# BTX.net
KiCad netlist of a schematic drawn in EAGLE
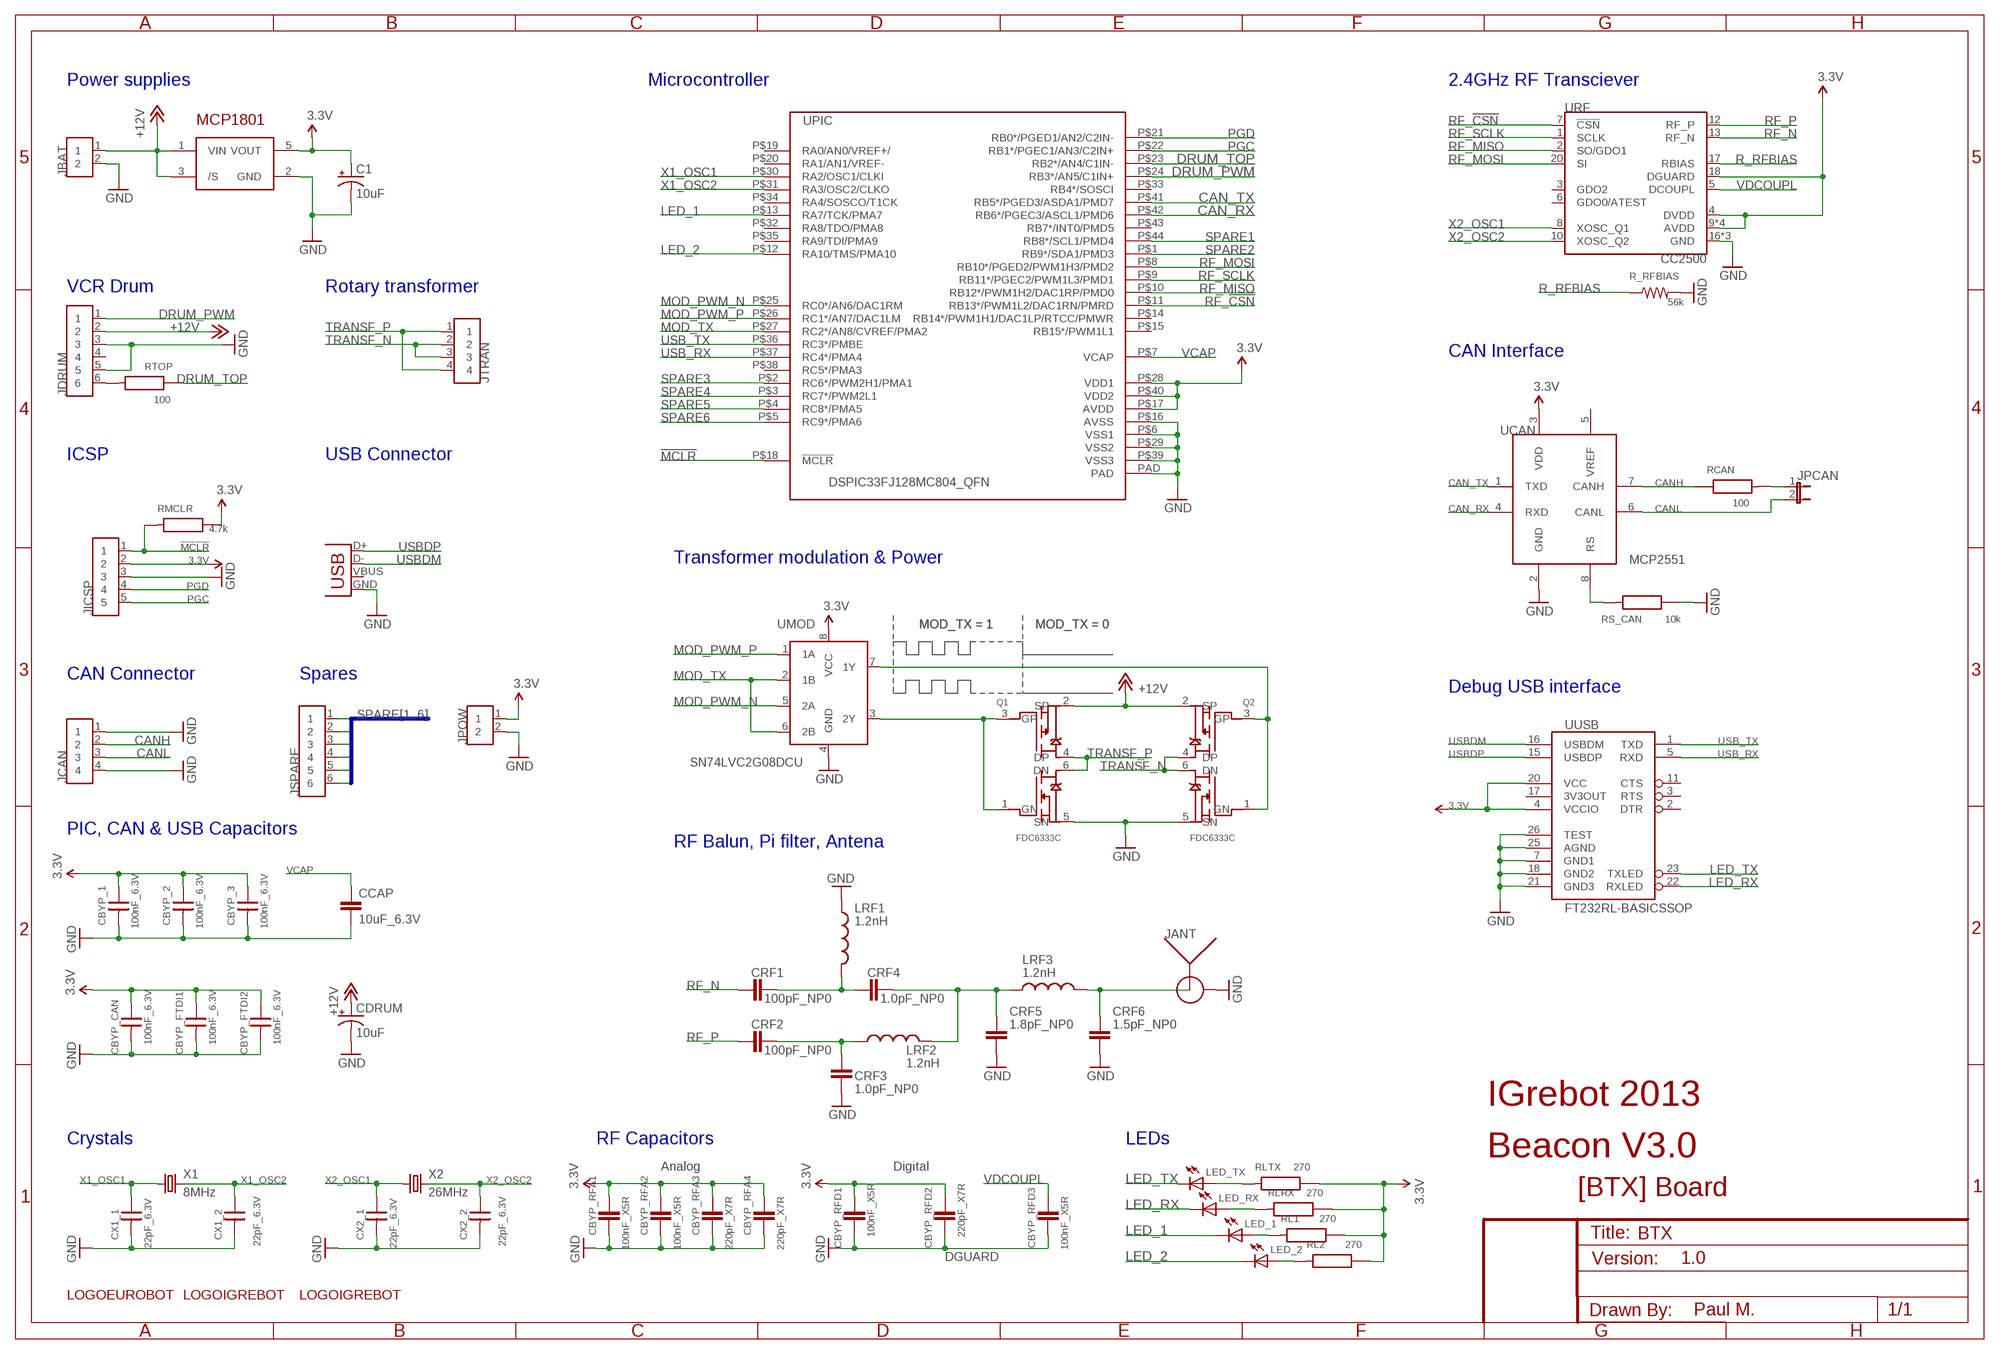
[diagram p0: schematic, sheet 1]

(export (version "E")
  (design (tool "Eeschema 10.0.6"))
  (components
    (comp (ref "C1")
      (value "10uF")
      (footprint "eagle-import:PANASONIC_C")
      (libsource (lib "eagle-import") (part "CAP_POLC"))
    )
    (comp (ref "CBYP_1")
      (value "100nF_6.3V")
      (footprint "eagle-import:R0603")
      (libsource (lib "eagle-import") (part "C0603"))
    )
    (comp (ref "CBYP_2")
      (value "100nF_6.3V")
      (footprint "eagle-import:R0603")
      (libsource (lib "eagle-import") (part "C0603"))
    )
    (comp (ref "CBYP_3")
      (value "100nF_6.3V")
      (footprint "eagle-import:R0603")
      (libsource (lib "eagle-import") (part "C0603"))
    )
    (comp (ref "CBYP_CAN")
      (value "100nF_6.3V")
      (footprint "eagle-import:R0603")
      (libsource (lib "eagle-import") (part "C0603"))
    )
    (comp (ref "CBYP_FTDI1")
      (value "100nF_6.3V")
      (footprint "eagle-import:R0603")
      (libsource (lib "eagle-import") (part "C0603"))
    )
    (comp (ref "CBYP_FTDI2")
      (value "100nF_6.3V")
      (footprint "eagle-import:R0603")
      (libsource (lib "eagle-import") (part "C0603"))
    )
    (comp (ref "CBYP_RFA1")
      (value "100nF_X5R")
      (footprint "eagle-import:0402-CAP")
      (libsource (lib "eagle-import") (part "SparkFun-Passives_CAP0402-CAP"))
    )
    (comp (ref "CBYP_RFA2")
      (value "100nF_X5R")
      (footprint "eagle-import:0402-CAP")
      (libsource (lib "eagle-import") (part "SparkFun-Passives_CAP0402-CAP"))
    )
    (comp (ref "CBYP_RFA3")
      (value "220pF_X7R")
      (footprint "eagle-import:0402-CAP")
      (libsource (lib "eagle-import") (part "SparkFun-Passives_CAP0402-CAP"))
    )
    (comp (ref "CBYP_RFA4")
      (value "220pF_X7R")
      (footprint "eagle-import:0402-CAP")
      (libsource (lib "eagle-import") (part "SparkFun-Passives_CAP0402-CAP"))
    )
    (comp (ref "CBYP_RFD1")
      (value "100nF_X5R")
      (footprint "eagle-import:0402-CAP")
      (libsource (lib "eagle-import") (part "SparkFun-Passives_CAP0402-CAP"))
    )
    (comp (ref "CBYP_RFD2")
      (value "220pF_X7R")
      (footprint "eagle-import:0402-CAP")
      (libsource (lib "eagle-import") (part "SparkFun-Passives_CAP0402-CAP"))
    )
    (comp (ref "CBYP_RFD3")
      (value "100nF_X5R")
      (footprint "eagle-import:0402-CAP")
      (libsource (lib "eagle-import") (part "SparkFun-Passives_CAP0402-CAP"))
    )
    (comp (ref "CCAP")
      (value "10uF_6.3V")
      (footprint "eagle-import:1206")
      (libsource (lib "eagle-import") (part "CAP1206"))
    )
    (comp (ref "CDRUM")
      (value "10uF")
      (footprint "eagle-import:PANASONIC_C")
      (libsource (lib "eagle-import") (part "CAP_POLC"))
    )
    (comp (ref "CRF1")
      (value "100pF_NP0")
      (footprint "eagle-import:0402-CAP")
      (libsource (lib "eagle-import") (part "SparkFun-Passives_CAP0402-CAP"))
    )
    (comp (ref "CRF2")
      (value "100pF_NP0")
      (footprint "eagle-import:0402-CAP")
      (libsource (lib "eagle-import") (part "SparkFun-Passives_CAP0402-CAP"))
    )
    (comp (ref "CRF3")
      (value "1.0pF_NP0")
      (footprint "eagle-import:0402-CAP")
      (libsource (lib "eagle-import") (part "SparkFun-Passives_CAP0402-CAP"))
    )
    (comp (ref "CRF4")
      (value "1.0pF_NP0")
      (footprint "eagle-import:0402-CAP")
      (libsource (lib "eagle-import") (part "SparkFun-Passives_CAP0402-CAP"))
    )
    (comp (ref "CRF5")
      (value "1.8pF_NP0")
      (footprint "eagle-import:0402-CAP")
      (libsource (lib "eagle-import") (part "SparkFun-Passives_CAP0402-CAP"))
    )
    (comp (ref "CRF6")
      (value "1.5pF_NP0")
      (footprint "eagle-import:0402-CAP")
      (libsource (lib "eagle-import") (part "SparkFun-Passives_CAP0402-CAP"))
    )
    (comp (ref "CX1_1")
      (value "22pF_6.3V")
      (footprint "eagle-import:R0603")
      (libsource (lib "eagle-import") (part "C0603"))
    )
    (comp (ref "CX1_2")
      (value "22pF_6.3V")
      (footprint "eagle-import:R0603")
      (libsource (lib "eagle-import") (part "C0603"))
    )
    (comp (ref "CX2_1")
      (value "22pF_6.3V")
      (footprint "eagle-import:R0603")
      (libsource (lib "eagle-import") (part "C0603"))
    )
    (comp (ref "CX2_2")
      (value "22pF_6.3V")
      (footprint "eagle-import:R0603")
      (libsource (lib "eagle-import") (part "C0603"))
    )
    (comp (ref "JANT")
      (value "ENG_CD_1814400_C1")
      (footprint "eagle-import:SMA-PCB-ANGLE")
      (libsource (lib "eagle-import") (part "ENG_CD_1814400_C1"))
    )
    (comp (ref "JBAT")
      (value "MULTICOMP_PA001-2")
      (footprint "eagle-import:CON2-5.00")
      (libsource (lib "eagle-import") (part "MULTICOMP_PA001-2"))
    )
    (comp (ref "JCAN")
      (value "SIL4")
      (footprint "eagle-import:CON4-2.54")
      (libsource (lib "eagle-import") (part "SIL4"))
    )
    (comp (ref "JDRUM")
      (value "SIL6")
      (footprint "eagle-import:CON6-2.54")
      (libsource (lib "eagle-import") (part "SIL6"))
    )
    (comp (ref "JICSP")
      (value "SIL5")
      (footprint "eagle-import:CON5-2.54")
      (libsource (lib "eagle-import") (part "SIL5"))
    )
    (comp (ref "JPCAN")
      (value "JUMPER-2PTH_LOCK")
      (footprint "eagle-import:1X02_LOCK")
      (libsource (lib "eagle-import") (part "JUMPER-2PTH_LOCK"))
    )
    (comp (ref "JPOW")
      (value "SIL2")
      (footprint "eagle-import:CON2-2.54")
      (libsource (lib "eagle-import") (part "SIL2"))
    )
    (comp (ref "JSPARE")
      (value "SIL6")
      (footprint "eagle-import:CON6-2.54")
      (libsource (lib "eagle-import") (part "SIL6"))
    )
    (comp (ref "JTRAN")
      (value "SIL4")
      (footprint "eagle-import:CON4-2.54")
      (libsource (lib "eagle-import") (part "SIL4"))
    )
    (comp (ref "JUSB")
      (value "USBSMD")
      (footprint "eagle-import:USB-MINIB")
      (libsource (lib "eagle-import") (part "USBSMD"))
    )
    (comp (ref "LED_1")
      (value "LED0603")
      (footprint "eagle-import:LED-0603")
      (libsource (lib "eagle-import") (part "LED0603"))
    )
    (comp (ref "LED_2")
      (value "LED0603")
      (footprint "eagle-import:LED-0603")
      (libsource (lib "eagle-import") (part "LED0603"))
    )
    (comp (ref "LED_RX")
      (value "LED0603")
      (footprint "eagle-import:LED-0603")
      (libsource (lib "eagle-import") (part "LED0603"))
    )
    (comp (ref "LED_TX")
      (value "LED0603")
      (footprint "eagle-import:LED-0603")
      (libsource (lib "eagle-import") (part "LED0603"))
    )
    (comp (ref "LRF1")
      (value "1.2nH")
      (footprint "eagle-import:C0402")
      (libsource (lib "eagle-import") (part "INDUCTOR0402"))
    )
    (comp (ref "LRF2")
      (value "1.2nH")
      (footprint "eagle-import:C0402")
      (libsource (lib "eagle-import") (part "INDUCTOR0402"))
    )
    (comp (ref "LRF3")
      (value "1.2nH")
      (footprint "eagle-import:C0402")
      (libsource (lib "eagle-import") (part "INDUCTOR0402"))
    )
    (comp (ref "Q1")
      (value "FDC6333C")
      (footprint "eagle-import:SSOT6")
      (libsource (lib "eagle-import") (part "FDC6333C"))
    )
    (comp (ref "Q2")
      (value "FDC6333C")
      (footprint "eagle-import:SSOT6")
      (libsource (lib "eagle-import") (part "FDC6333C"))
    )
    (comp (ref "RCAN")
      (value "100")
      (footprint "eagle-import:R0603")
      (libsource (lib "eagle-import") (part "R0603"))
    )
    (comp (ref "RL1")
      (value "270")
      (footprint "eagle-import:R0603")
      (libsource (lib "eagle-import") (part "R0603"))
    )
    (comp (ref "RL2")
      (value "270")
      (footprint "eagle-import:R0603")
      (libsource (lib "eagle-import") (part "R0603"))
    )
    (comp (ref "RLRX")
      (value "270")
      (footprint "eagle-import:R0603")
      (libsource (lib "eagle-import") (part "R0603"))
    )
    (comp (ref "RLTX")
      (value "270")
      (footprint "eagle-import:R0603")
      (libsource (lib "eagle-import") (part "R0603"))
    )
    (comp (ref "RMCLR")
      (value "4.7k")
      (footprint "eagle-import:R0603")
      (libsource (lib "eagle-import") (part "R0603"))
    )
    (comp (ref "RS_CAN")
      (value "10k")
      (footprint "eagle-import:R0603")
      (libsource (lib "eagle-import") (part "R0603"))
    )
    (comp (ref "RTOP")
      (value "100")
      (footprint "eagle-import:R0603")
      (libsource (lib "eagle-import") (part "R0603"))
    )
    (comp (ref "R_RFBIAS")
      (value "56k")
      (footprint "eagle-import:0402-RES")
      (libsource (lib "eagle-import") (part "RESISTOR0402-RES"))
    )
    (comp (ref "U$3")
      (value "LOGOEUROBOT")
      (footprint "eagle-import:LOGO_EUROBOT_1")
      (libsource (lib "eagle-import") (part "LOGOEUROBOT"))
    )
    (comp (ref "U$5")
      (value "LOGOIGREBOT")
      (footprint "eagle-import:LOGO_IGREBOT")
      (libsource (lib "eagle-import") (part "LOGOIGREBOT"))
    )
    (comp (ref "U$9")
      (value "LOGOIGREBOT")
      (footprint "eagle-import:LOGO_IGREBOT")
      (libsource (lib "eagle-import") (part "LOGOIGREBOT"))
    )
    (comp (ref "UCAN")
      (value "MCP2551")
      (footprint "eagle-import:SO-08")
      (libsource (lib "eagle-import") (part "MCP2551"))
    )
    (comp (ref "UMOD")
      (value "SN74LVC2G08DCU")
      (footprint "eagle-import:DCU8")
      (libsource (lib "eagle-import") (part "SN74LVC2G08DCU"))
    )
    (comp (ref "UPIC")
      (value "DSPIC33FJ128MC804_QFN")
      (footprint "eagle-import:QFN44-8X8")
      (libsource (lib "eagle-import") (part "DSPIC33FJ128MC804_QFN"))
    )
    (comp (ref "UREG")
      (value "MCP1801")
      (footprint "eagle-import:SOT23-5L")
      (libsource (lib "eagle-import") (part "MCP1801"))
    )
    (comp (ref "URF")
      (value "CC2500")
      (footprint "eagle-import:QFN20-0.5")
      (libsource (lib "eagle-import") (part "CC2500"))
    )
    (comp (ref "UUSB")
      (value "FT232RL-BASICSSOP")
      (footprint "eagle-import:SSOP28DB")
      (libsource (lib "eagle-import") (part "FT232RL-BASICSSOP"))
    )
    (comp (ref "X1")
      (value "8MHz")
      (footprint "eagle-import:XTAL_4.9-1.8")
      (libsource (lib "eagle-import") (part "XTAL4.8_1.8"))
    )
    (comp (ref "X2")
      (value "26MHz")
      (footprint "eagle-import:XTAL_4.9-1.8")
      (libsource (lib "eagle-import") (part "XTAL4.8_1.8"))
    )
  )
  (nets
    (net (code "1") (name "+12V") (class "Default")
      (node (ref "CDRUM") (pin "+") (pinfunction "+_+") (pintype "passive"))
      (node (ref "JBAT") (pin "1") (pinfunction "1_1") (pintype "bidirectional"))
      (node (ref "JDRUM") (pin "2") (pinfunction "2_2") (pintype "bidirectional"))
      (node (ref "Q1") (pin "2") (pinfunction "SP_2") (pintype "bidirectional"))
      (node (ref "Q2") (pin "2") (pinfunction "SP_2") (pintype "bidirectional"))
      (node (ref "UREG") (pin "1") (pinfunction "VIN_1") (pintype "bidirectional"))
      (node (ref "UREG") (pin "3") (pinfunction "/S_3") (pintype "bidirectional"))
    )
    (net (code "2") (name "/CANH") (class "Default")
      (node (ref "JCAN") (pin "2") (pinfunction "2_2") (pintype "bidirectional"))
      (node (ref "RCAN") (pin "1") (pinfunction "1_1") (pintype "bidirectional"))
      (node (ref "UCAN") (pin "7") (pinfunction "CANH_7") (pintype "bidirectional"))
    )
    (net (code "3") (name "/CANL") (class "Default")
      (node (ref "JCAN") (pin "3") (pinfunction "3_3") (pintype "bidirectional"))
      (node (ref "JPCAN") (pin "2") (pinfunction "2_2") (pintype "passive"))
      (node (ref "UCAN") (pin "6") (pinfunction "CANL_6") (pintype "bidirectional"))
    )
    (net (code "4") (name "/CAN_RX") (class "Default")
      (node (ref "UCAN") (pin "4") (pinfunction "RXD_4") (pintype "bidirectional"))
      (node (ref "UPIC") (pin "P$42") (pinfunction "RB6*/PGEC3/ASCL1/PMD6_P$42") (pintype "bidirectional"))
    )
    (net (code "5") (name "/CAN_TX") (class "Default")
      (node (ref "UCAN") (pin "1") (pinfunction "TXD_1") (pintype "bidirectional"))
      (node (ref "UPIC") (pin "P$41") (pinfunction "RB5*/PGED3/ASDA1/PMD7_P$41") (pintype "bidirectional"))
    )
    (net (code "6") (name "/DRUM_PWM") (class "Default")
      (node (ref "JDRUM") (pin "1") (pinfunction "1_1") (pintype "bidirectional"))
      (node (ref "UPIC") (pin "P$24") (pinfunction "RB3*/AN5/C1IN+_P$24") (pintype "bidirectional"))
    )
    (net (code "7") (name "/DRUM_TOP") (class "Default")
      (node (ref "RTOP") (pin "1") (pinfunction "1_1") (pintype "bidirectional"))
      (node (ref "UPIC") (pin "P$23") (pinfunction "RB2*/AN4/C1IN-_P$23") (pintype "bidirectional"))
    )
    (net (code "8") (name "/LED_1") (class "Default")
      (node (ref "LED_1") (pin "C") (pinfunction "C_C") (pintype "passive"))
      (node (ref "UPIC") (pin "P$13") (pinfunction "RA7/TCK/PMA7_P$13") (pintype "bidirectional"))
    )
    (net (code "9") (name "/LED_2") (class "Default")
      (node (ref "LED_2") (pin "C") (pinfunction "C_C") (pintype "passive"))
      (node (ref "UPIC") (pin "P$12") (pinfunction "RA10/TMS/PMA10_P$12") (pintype "bidirectional"))
    )
    (net (code "10") (name "/LED_RX") (class "Default")
      (node (ref "LED_RX") (pin "C") (pinfunction "C_C") (pintype "passive"))
      (node (ref "UUSB") (pin "22") (pinfunction "RXLED_22") (pintype "bidirectional"))
    )
    (net (code "11") (name "/LED_TX") (class "Default")
      (node (ref "LED_TX") (pin "C") (pinfunction "C_C") (pintype "passive"))
      (node (ref "UUSB") (pin "23") (pinfunction "TXLED_23") (pintype "bidirectional"))
    )
    (net (code "12") (name "/MOD_PWM_N") (class "Default")
      (node (ref "UMOD") (pin "5") (pinfunction "2A_5") (pintype "bidirectional"))
      (node (ref "UPIC") (pin "P$25") (pinfunction "RC0*/AN6/DAC1RM_P$25") (pintype "bidirectional"))
    )
    (net (code "13") (name "/MOD_PWM_P") (class "Default")
      (node (ref "UMOD") (pin "1") (pinfunction "1A_1") (pintype "bidirectional"))
      (node (ref "UPIC") (pin "P$26") (pinfunction "RC1*/AN7/DAC1LM_P$26") (pintype "bidirectional"))
    )
    (net (code "14") (name "/MOD_TX") (class "Default")
      (node (ref "UMOD") (pin "2") (pinfunction "1B_2") (pintype "bidirectional"))
      (node (ref "UMOD") (pin "6") (pinfunction "2B_6") (pintype "bidirectional"))
      (node (ref "UPIC") (pin "P$27") (pinfunction "RC2*/AN8/CVREF/PMA2_P$27") (pintype "bidirectional"))
    )
    (net (code "15") (name "/PGC") (class "Default")
      (node (ref "JICSP") (pin "5") (pinfunction "5_5") (pintype "bidirectional"))
      (node (ref "UPIC") (pin "P$22") (pinfunction "RB1*/PGEC1/AN3/C2IN+_P$22") (pintype "bidirectional"))
    )
    (net (code "16") (name "/PGD") (class "Default")
      (node (ref "JICSP") (pin "4") (pinfunction "4_4") (pintype "bidirectional"))
      (node (ref "UPIC") (pin "P$21") (pinfunction "RB0*/PGED1/AN2/C2IN-_P$21") (pintype "bidirectional"))
    )
    (net (code "17") (name "/RF_MISO") (class "Default")
      (node (ref "UPIC") (pin "P$10") (pinfunction "RB12*/PWM1H2/DAC1RP/PMD0_P$10") (pintype "bidirectional"))
      (node (ref "URF") (pin "2") (pinfunction "SO/GDO1_2") (pintype "bidirectional"))
    )
    (net (code "18") (name "/RF_MOSI") (class "Default")
      (node (ref "UPIC") (pin "P$8") (pinfunction "RB10*/PGED2/PWM1H3/PMD2_P$8") (pintype "bidirectional"))
      (node (ref "URF") (pin "20") (pinfunction "SI_20") (pintype "bidirectional"))
    )
    (net (code "19") (name "/RF_N") (class "Default")
      (node (ref "CRF1") (pin "1") (pinfunction "1_1") (pintype "passive"))
      (node (ref "URF") (pin "13") (pinfunction "RF_N_13") (pintype "bidirectional"))
    )
    (net (code "20") (name "/RF_P") (class "Default")
      (node (ref "CRF2") (pin "1") (pinfunction "1_1") (pintype "passive"))
      (node (ref "URF") (pin "12") (pinfunction "RF_P_12") (pintype "bidirectional"))
    )
    (net (code "21") (name "/RF_SCLK") (class "Default")
      (node (ref "UPIC") (pin "P$9") (pinfunction "RB11*/PGEC2/PWM1L3/PMD1_P$9") (pintype "bidirectional"))
      (node (ref "URF") (pin "1") (pinfunction "SCLK_1") (pintype "bidirectional"))
    )
    (net (code "22") (name "/RF_~{CSN}") (class "Default")
      (node (ref "UPIC") (pin "P$11") (pinfunction "RB13*/PWM1L2/DAC1RN/PMRD_P$11") (pintype "bidirectional"))
      (node (ref "URF") (pin "7") (pinfunction "~{CSN}_7") (pintype "bidirectional"))
    )
    (net (code "23") (name "/R_RFBIAS") (class "Default")
      (node (ref "R_RFBIAS") (pin "1") (pinfunction "1_1") (pintype "passive"))
      (node (ref "URF") (pin "17") (pinfunction "RBIAS_17") (pintype "bidirectional"))
    )
    (net (code "24") (name "/SPARE1") (class "Default")
      (node (ref "JSPARE") (pin "1") (pinfunction "1_1") (pintype "bidirectional"))
      (node (ref "UPIC") (pin "P$44") (pinfunction "RB8*/SCL1/PMD4_P$44") (pintype "bidirectional"))
    )
    (net (code "25") (name "/SPARE2") (class "Default")
      (node (ref "JSPARE") (pin "2") (pinfunction "2_2") (pintype "bidirectional"))
      (node (ref "UPIC") (pin "P$1") (pinfunction "RB9*/SDA1/PMD3_P$1") (pintype "bidirectional"))
    )
    (net (code "26") (name "/SPARE3") (class "Default")
      (node (ref "JSPARE") (pin "3") (pinfunction "3_3") (pintype "bidirectional"))
      (node (ref "UPIC") (pin "P$2") (pinfunction "RC6*/PWM2H1/PMA1_P$2") (pintype "bidirectional"))
    )
    (net (code "27") (name "/SPARE4") (class "Default")
      (node (ref "JSPARE") (pin "4") (pinfunction "4_4") (pintype "bidirectional"))
      (node (ref "UPIC") (pin "P$3") (pinfunction "RC7*/PWM2L1_P$3") (pintype "bidirectional"))
    )
    (net (code "28") (name "/SPARE5") (class "Default")
      (node (ref "JSPARE") (pin "5") (pinfunction "5_5") (pintype "bidirectional"))
      (node (ref "UPIC") (pin "P$4") (pinfunction "RC8*/PMA5_P$4") (pintype "bidirectional"))
    )
    (net (code "29") (name "/SPARE6") (class "Default")
      (node (ref "JSPARE") (pin "6") (pinfunction "6_6") (pintype "bidirectional"))
      (node (ref "UPIC") (pin "P$5") (pinfunction "RC9*/PMA6_P$5") (pintype "bidirectional"))
    )
    (net (code "31") (name "/TRANSF_N") (class "Default")
      (node (ref "JTRAN") (pin "2") (pinfunction "2_2") (pintype "bidirectional"))
      (node (ref "JTRAN") (pin "3") (pinfunction "3_3") (pintype "bidirectional"))
      (node (ref "Q2") (pin "4") (pinfunction "DP_4") (pintype "bidirectional"))
      (node (ref "Q2") (pin "6") (pinfunction "DN_6") (pintype "bidirectional"))
    )
    (net (code "32") (name "/TRANSF_P") (class "Default")
      (node (ref "JTRAN") (pin "1") (pinfunction "1_1") (pintype "bidirectional"))
      (node (ref "JTRAN") (pin "4") (pinfunction "4_4") (pintype "bidirectional"))
      (node (ref "Q1") (pin "4") (pinfunction "DP_4") (pintype "bidirectional"))
      (node (ref "Q1") (pin "6") (pinfunction "DN_6") (pintype "bidirectional"))
    )
    (net (code "33") (name "/USBDM") (class "Default")
      (node (ref "JUSB") (pin "D-") (pinfunction "D-_D-") (pintype "bidirectional"))
      (node (ref "UUSB") (pin "16") (pinfunction "USBDM_16") (pintype "bidirectional"))
    )
    (net (code "34") (name "/USBDP") (class "Default")
      (node (ref "JUSB") (pin "D+") (pinfunction "D+_D+") (pintype "bidirectional"))
      (node (ref "UUSB") (pin "15") (pinfunction "USBDP_15") (pintype "bidirectional"))
    )
    (net (code "35") (name "/USB_RX") (class "Default")
      (node (ref "UPIC") (pin "P$37") (pinfunction "RC4*/PMA4_P$37") (pintype "bidirectional"))
      (node (ref "UUSB") (pin "5") (pinfunction "RXD_5") (pintype "input"))
    )
    (net (code "36") (name "/USB_TX") (class "Default")
      (node (ref "UPIC") (pin "P$36") (pinfunction "RC3*/PMBE_P$36") (pintype "bidirectional"))
      (node (ref "UUSB") (pin "1") (pinfunction "TXD_1") (pintype "output"))
    )
    (net (code "37") (name "/VCAP") (class "Default")
      (node (ref "CCAP") (pin "1") (pinfunction "1_1") (pintype "passive"))
      (node (ref "UPIC") (pin "P$7") (pinfunction "VCAP_P$7") (pintype "bidirectional"))
    )
    (net (code "38") (name "/VDCOUPL") (class "Default")
      (node (ref "CBYP_RFD3") (pin "2") (pinfunction "2_2") (pintype "passive"))
      (node (ref "URF") (pin "5") (pinfunction "DCOUPL_5") (pintype "bidirectional"))
    )
    (net (code "39") (name "/X1_OSC1") (class "Default")
      (node (ref "CX1_1") (pin "1") (pinfunction "1_1") (pintype "bidirectional"))
      (node (ref "UPIC") (pin "P$30") (pinfunction "RA2/OSC1/CLKI_P$30") (pintype "bidirectional"))
      (node (ref "X1") (pin "P$1") (pinfunction "1_P$1") (pintype "passive"))
    )
    (net (code "40") (name "/X1_OSC2") (class "Default")
      (node (ref "CX1_2") (pin "1") (pinfunction "1_1") (pintype "bidirectional"))
      (node (ref "UPIC") (pin "P$31") (pinfunction "RA3/OSC2/CLKO_P$31") (pintype "bidirectional"))
      (node (ref "X1") (pin "P$2") (pinfunction "2_P$2") (pintype "passive"))
    )
    (net (code "41") (name "/X2_OSC1") (class "Default")
      (node (ref "CX2_1") (pin "1") (pinfunction "1_1") (pintype "bidirectional"))
      (node (ref "URF") (pin "8") (pinfunction "XOSC_Q1_8") (pintype "bidirectional"))
      (node (ref "X2") (pin "P$1") (pinfunction "1_P$1") (pintype "passive"))
    )
    (net (code "42") (name "/X2_OSC2") (class "Default")
      (node (ref "CX2_2") (pin "1") (pinfunction "1_1") (pintype "bidirectional"))
      (node (ref "URF") (pin "10") (pinfunction "XOSC_Q2_10") (pintype "bidirectional"))
      (node (ref "X2") (pin "P$2") (pinfunction "2_P$2") (pintype "passive"))
    )
    (net (code "43") (name "/~{MCLR}") (class "Default")
      (node (ref "JICSP") (pin "1") (pinfunction "1_1") (pintype "bidirectional"))
      (node (ref "RMCLR") (pin "2") (pinfunction "2_2") (pintype "bidirectional"))
      (node (ref "UPIC") (pin "P$18") (pinfunction "~{MCLR}_P$18") (pintype "bidirectional"))
    )
    (net (code "44") (name "3.3V") (class "Default")
      (node (ref "C1") (pin "+") (pinfunction "+_+") (pintype "passive"))
      (node (ref "CBYP_1") (pin "1") (pinfunction "1_1") (pintype "bidirectional"))
      (node (ref "CBYP_2") (pin "1") (pinfunction "1_1") (pintype "bidirectional"))
      (node (ref "CBYP_3") (pin "1") (pinfunction "1_1") (pintype "bidirectional"))
      (node (ref "CBYP_CAN") (pin "1") (pinfunction "1_1") (pintype "bidirectional"))
      (node (ref "CBYP_FTDI1") (pin "1") (pinfunction "1_1") (pintype "bidirectional"))
      (node (ref "CBYP_FTDI2") (pin "1") (pinfunction "1_1") (pintype "bidirectional"))
      (node (ref "CBYP_RFA1") (pin "2") (pinfunction "2_2") (pintype "passive"))
      (node (ref "CBYP_RFA2") (pin "2") (pinfunction "2_2") (pintype "passive"))
      (node (ref "CBYP_RFA3") (pin "2") (pinfunction "2_2") (pintype "passive"))
      (node (ref "CBYP_RFA4") (pin "2") (pinfunction "2_2") (pintype "passive"))
      (node (ref "CBYP_RFD1") (pin "2") (pinfunction "2_2") (pintype "passive"))
      (node (ref "CBYP_RFD2") (pin "2") (pinfunction "2_2") (pintype "passive"))
      (node (ref "JICSP") (pin "2") (pinfunction "2_2") (pintype "bidirectional"))
      (node (ref "JPOW") (pin "1") (pinfunction "1_1") (pintype "bidirectional"))
      (node (ref "RL1") (pin "1") (pinfunction "1_1") (pintype "bidirectional"))
      (node (ref "RL2") (pin "1") (pinfunction "1_1") (pintype "bidirectional"))
      (node (ref "RLRX") (pin "1") (pinfunction "1_1") (pintype "bidirectional"))
      (node (ref "RLTX") (pin "1") (pinfunction "1_1") (pintype "bidirectional"))
      (node (ref "RMCLR") (pin "1") (pinfunction "1_1") (pintype "bidirectional"))
      (node (ref "UCAN") (pin "3") (pinfunction "VDD_3") (pintype "bidirectional"))
      (node (ref "UMOD") (pin "8") (pinfunction "VCC_8") (pintype "bidirectional"))
      (node (ref "UPIC") (pin "P$17") (pinfunction "AVDD_P$17") (pintype "bidirectional"))
      (node (ref "UPIC") (pin "P$28") (pinfunction "VDD1_P$28") (pintype "bidirectional"))
      (node (ref "UPIC") (pin "P$40") (pinfunction "VDD2_P$40") (pintype "bidirectional"))
      (node (ref "UREG") (pin "5") (pinfunction "VOUT_5") (pintype "bidirectional"))
      (node (ref "URF") (pin "11") (pinfunction "AVDD_11") (pintype "bidirectional"))
      (node (ref "URF") (pin "14") (pinfunction "AVDD_14") (pintype "bidirectional"))
      (node (ref "URF") (pin "15") (pinfunction "AVDD_15") (pintype "bidirectional"))
      (node (ref "URF") (pin "18") (pinfunction "DGUARD_18") (pintype "bidirectional"))
      (node (ref "URF") (pin "4") (pinfunction "DVDD_4") (pintype "bidirectional"))
      (node (ref "URF") (pin "9") (pinfunction "AVDD_9") (pintype "bidirectional"))
      (node (ref "UUSB") (pin "20") (pinfunction "VCC_20") (pintype "power_in"))
      (node (ref "UUSB") (pin "4") (pinfunction "VCCIO_4") (pintype "power_in"))
    )
    (net (code "45") (name "GND") (class "Default")
      (node (ref "C1") (pin "-") (pinfunction "-_-") (pintype "passive"))
      (node (ref "CBYP_1") (pin "2") (pinfunction "2_2") (pintype "bidirectional"))
      (node (ref "CBYP_2") (pin "2") (pinfunction "2_2") (pintype "bidirectional"))
      (node (ref "CBYP_3") (pin "2") (pinfunction "2_2") (pintype "bidirectional"))
      (node (ref "CBYP_CAN") (pin "2") (pinfunction "2_2") (pintype "bidirectional"))
      (node (ref "CBYP_FTDI1") (pin "2") (pinfunction "2_2") (pintype "bidirectional"))
      (node (ref "CBYP_FTDI2") (pin "2") (pinfunction "2_2") (pintype "bidirectional"))
      (node (ref "CBYP_RFA1") (pin "1") (pinfunction "1_1") (pintype "passive"))
      (node (ref "CBYP_RFA2") (pin "1") (pinfunction "1_1") (pintype "passive"))
      (node (ref "CBYP_RFA3") (pin "1") (pinfunction "1_1") (pintype "passive"))
      (node (ref "CBYP_RFA4") (pin "1") (pinfunction "1_1") (pintype "passive"))
      (node (ref "CBYP_RFD1") (pin "1") (pinfunction "1_1") (pintype "passive"))
      (node (ref "CBYP_RFD2") (pin "1") (pinfunction "1_1") (pintype "passive"))
      (node (ref "CBYP_RFD3") (pin "1") (pinfunction "1_1") (pintype "passive"))
      (node (ref "CCAP") (pin "2") (pinfunction "2_2") (pintype "passive"))
      (node (ref "CDRUM") (pin "-") (pinfunction "-_-") (pintype "passive"))
      (node (ref "CRF3") (pin "1") (pinfunction "1_1") (pintype "passive"))
      (node (ref "CRF5") (pin "1") (pinfunction "1_1") (pintype "passive"))
      (node (ref "CRF6") (pin "1") (pinfunction "1_1") (pintype "passive"))
      (node (ref "CX1_1") (pin "2") (pinfunction "2_2") (pintype "bidirectional"))
      (node (ref "CX1_2") (pin "2") (pinfunction "2_2") (pintype "bidirectional"))
      (node (ref "CX2_1") (pin "2") (pinfunction "2_2") (pintype "bidirectional"))
      (node (ref "CX2_2") (pin "2") (pinfunction "2_2") (pintype "bidirectional"))
      (node (ref "JANT") (pin "B1") (pinfunction "B_B1") (pintype "bidirectional"))
      (node (ref "JANT") (pin "B2") (pinfunction "B_B2") (pintype "bidirectional"))
      (node (ref "JANT") (pin "B3") (pinfunction "B_B3") (pintype "bidirectional"))
      (node (ref "JANT") (pin "B4") (pinfunction "B_B4") (pintype "bidirectional"))
      (node (ref "JBAT") (pin "2") (pinfunction "2_2") (pintype "bidirectional"))
      (node (ref "JCAN") (pin "1") (pinfunction "1_1") (pintype "bidirectional"))
      (node (ref "JCAN") (pin "4") (pinfunction "4_4") (pintype "bidirectional"))
      (node (ref "JDRUM") (pin "3") (pinfunction "3_3") (pintype "bidirectional"))
      (node (ref "JDRUM") (pin "5") (pinfunction "5_5") (pintype "bidirectional"))
      (node (ref "JICSP") (pin "3") (pinfunction "3_3") (pintype "bidirectional"))
      (node (ref "JPOW") (pin "2") (pinfunction "2_2") (pintype "bidirectional"))
      (node (ref "JUSB") (pin "GND") (pinfunction "GND_GND") (pintype "bidirectional"))
      (node (ref "LRF1") (pin "1") (pinfunction "1_1") (pintype "passive"))
      (node (ref "Q1") (pin "5") (pinfunction "SN_5") (pintype "bidirectional"))
      (node (ref "Q2") (pin "5") (pinfunction "SN_5") (pintype "bidirectional"))
      (node (ref "RS_CAN") (pin "1") (pinfunction "1_1") (pintype "bidirectional"))
      (node (ref "R_RFBIAS") (pin "2") (pinfunction "2_2") (pintype "passive"))
      (node (ref "UCAN") (pin "2") (pinfunction "GND_2") (pintype "bidirectional"))
      (node (ref "UMOD") (pin "4") (pinfunction "GND_4") (pintype "bidirectional"))
      (node (ref "UPIC") (pin "P$16") (pinfunction "AVSS_P$16") (pintype "bidirectional"))
      (node (ref "UPIC") (pin "P$29") (pinfunction "VSS2_P$29") (pintype "bidirectional"))
      (node (ref "UPIC") (pin "P$39") (pinfunction "VSS3_P$39") (pintype "bidirectional"))
      (node (ref "UPIC") (pin "P$6") (pinfunction "VSS1_P$6") (pintype "bidirectional"))
      (node (ref "UPIC") (pin "PAD") (pinfunction "PAD_PAD") (pintype "bidirectional"))
      (node (ref "UREG") (pin "2") (pinfunction "GND_2") (pintype "bidirectional"))
      (node (ref "URF") (pin "16") (pinfunction "GND_16") (pintype "bidirectional"))
      (node (ref "URF") (pin "19") (pinfunction "GND_19") (pintype "bidirectional"))
      (node (ref "URF") (pin "PAD") (pinfunction "GND_PAD") (pintype "bidirectional"))
      (node (ref "UUSB") (pin "18") (pinfunction "GND2_18") (pintype "power_in"))
      (node (ref "UUSB") (pin "21") (pinfunction "GND3_21") (pintype "power_in"))
      (node (ref "UUSB") (pin "25") (pinfunction "AGND_25") (pintype "power_in"))
      (node (ref "UUSB") (pin "26") (pinfunction "TEST_26") (pintype "input"))
      (node (ref "UUSB") (pin "7") (pinfunction "GND1_7") (pintype "power_in"))
    )
    (net (code "46") (name "Net-(CRF1-Pad2)") (class "Default")
      (node (ref "CRF1") (pin "2") (pinfunction "2_2") (pintype "passive"))
      (node (ref "CRF4") (pin "2") (pinfunction "2_2") (pintype "passive"))
      (node (ref "LRF1") (pin "2") (pinfunction "2_2") (pintype "passive"))
    )
    (net (code "47") (name "Net-(CRF2-Pad2)") (class "Default")
      (node (ref "CRF2") (pin "2") (pinfunction "2_2") (pintype "passive"))
      (node (ref "CRF3") (pin "2") (pinfunction "2_2") (pintype "passive"))
      (node (ref "LRF2") (pin "1") (pinfunction "1_1") (pintype "passive"))
    )
    (net (code "48") (name "Net-(CRF4-Pad1)") (class "Default")
      (node (ref "CRF4") (pin "1") (pinfunction "1_1") (pintype "passive"))
      (node (ref "CRF5") (pin "2") (pinfunction "2_2") (pintype "passive"))
      (node (ref "LRF2") (pin "2") (pinfunction "2_2") (pintype "passive"))
      (node (ref "LRF3") (pin "1") (pinfunction "1_1") (pintype "passive"))
    )
    (net (code "49") (name "Net-(CRF6-Pad2)") (class "Default")
      (node (ref "CRF6") (pin "2") (pinfunction "2_2") (pintype "passive"))
      (node (ref "JANT") (pin "A") (pinfunction "A_A") (pintype "bidirectional"))
      (node (ref "LRF3") (pin "2") (pinfunction "2_2") (pintype "passive"))
    )
    (net (code "50") (name "Net-(JDRUM-Pad6)") (class "Default")
      (node (ref "JDRUM") (pin "6") (pinfunction "6_6") (pintype "bidirectional"))
      (node (ref "RTOP") (pin "2") (pinfunction "2_2") (pintype "bidirectional"))
    )
    (net (code "51") (name "Net-(JPCAN-Pad1)") (class "Default")
      (node (ref "JPCAN") (pin "1") (pinfunction "1_1") (pintype "passive"))
      (node (ref "RCAN") (pin "2") (pinfunction "2_2") (pintype "bidirectional"))
    )
    (net (code "52") (name "Net-(LED_1-PadA)") (class "Default")
      (node (ref "LED_1") (pin "A") (pinfunction "A_A") (pintype "passive"))
      (node (ref "RL1") (pin "2") (pinfunction "2_2") (pintype "bidirectional"))
    )
    (net (code "53") (name "Net-(LED_2-PadA)") (class "Default")
      (node (ref "LED_2") (pin "A") (pinfunction "A_A") (pintype "passive"))
      (node (ref "RL2") (pin "2") (pinfunction "2_2") (pintype "bidirectional"))
    )
    (net (code "54") (name "Net-(LED_RX-PadA)") (class "Default")
      (node (ref "LED_RX") (pin "A") (pinfunction "A_A") (pintype "passive"))
      (node (ref "RLRX") (pin "2") (pinfunction "2_2") (pintype "bidirectional"))
    )
    (net (code "55") (name "Net-(LED_TX-PadA)") (class "Default")
      (node (ref "LED_TX") (pin "A") (pinfunction "A_A") (pintype "passive"))
      (node (ref "RLTX") (pin "2") (pinfunction "2_2") (pintype "bidirectional"))
    )
    (net (code "56") (name "Net-(Q1-GN)") (class "Default")
      (node (ref "Q1") (pin "1") (pinfunction "GN_1") (pintype "bidirectional"))
      (node (ref "Q1") (pin "3") (pinfunction "GP_3") (pintype "bidirectional"))
      (node (ref "UMOD") (pin "3") (pinfunction "2Y_3") (pintype "bidirectional"))
    )
    (net (code "57") (name "Net-(Q2-GN)") (class "Default")
      (node (ref "Q2") (pin "1") (pinfunction "GN_1") (pintype "bidirectional"))
      (node (ref "Q2") (pin "3") (pinfunction "GP_3") (pintype "bidirectional"))
      (node (ref "UMOD") (pin "7") (pinfunction "1Y_7") (pintype "bidirectional"))
    )
    (net (code "58") (name "Net-(UCAN-RS)") (class "Default")
      (node (ref "RS_CAN") (pin "2") (pinfunction "2_2") (pintype "bidirectional"))
      (node (ref "UCAN") (pin "8") (pinfunction "RS_8") (pintype "bidirectional"))
    )
    (net (code "59") (name "unconnected-(JDRUM-Pad4)") (class "Default")
      (node (ref "JDRUM") (pin "4") (pinfunction "4_4") (pintype "bidirectional"))
    )
    (net (code "60") (name "unconnected-(JUSB-PadVBUS)") (class "Default")
      (node (ref "JUSB") (pin "VBUS") (pinfunction "VBUS_VBUS") (pintype "bidirectional"))
    )
    (net (code "61") (name "unconnected-(UCAN-VREF-Pad5)") (class "Default")
      (node (ref "UCAN") (pin "5") (pinfunction "VREF_5") (pintype "bidirectional"))
    )
    (net (code "62") (name "unconnected-(UPIC-RA0{slash}AN0{slash}VREF+{slash}-PadP$19)") (class "Default")
      (node (ref "UPIC") (pin "P$19") (pinfunction "RA0/AN0/VREF+/_P$19") (pintype "bidirectional"))
    )
    (net (code "63") (name "unconnected-(UPIC-RA1{slash}AN1{slash}VREF--PadP$20)") (class "Default")
      (node (ref "UPIC") (pin "P$20") (pinfunction "RA1/AN1/VREF-_P$20") (pintype "bidirectional"))
    )
    (net (code "64") (name "unconnected-(UPIC-RA4{slash}SOSCO{slash}T1CK-PadP$34)") (class "Default")
      (node (ref "UPIC") (pin "P$34") (pinfunction "RA4/SOSCO/T1CK_P$34") (pintype "bidirectional"))
    )
    (net (code "65") (name "unconnected-(UPIC-RA8{slash}TDO{slash}PMA8-PadP$32)") (class "Default")
      (node (ref "UPIC") (pin "P$32") (pinfunction "RA8/TDO/PMA8_P$32") (pintype "bidirectional"))
    )
    (net (code "66") (name "unconnected-(UPIC-RA9{slash}TDI{slash}PMA9-PadP$35)") (class "Default")
      (node (ref "UPIC") (pin "P$35") (pinfunction "RA9/TDI/PMA9_P$35") (pintype "bidirectional"))
    )
    (net (code "67") (name "unconnected-(UPIC-RB4*{slash}SOSCI-PadP$33)") (class "Default")
      (node (ref "UPIC") (pin "P$33") (pinfunction "RB4*/SOSCI_P$33") (pintype "bidirectional"))
    )
    (net (code "68") (name "unconnected-(UPIC-RB7*{slash}INT0{slash}PMD5-PadP$43)") (class "Default")
      (node (ref "UPIC") (pin "P$43") (pinfunction "RB7*/INT0/PMD5_P$43") (pintype "bidirectional"))
    )
    (net (code "69") (name "unconnected-(UPIC-RB14*{slash}PWM1H1{slash}DAC1LP{slash}RTCC{slash}PMWR-PadP$14)") (class "Default")
      (node (ref "UPIC") (pin "P$14") (pinfunction "RB14*/PWM1H1/DAC1LP/RTCC/PMWR_P$14") (pintype "bidirectional"))
    )
    (net (code "70") (name "unconnected-(UPIC-RB15*{slash}PWM1L1-PadP$15)") (class "Default")
      (node (ref "UPIC") (pin "P$15") (pinfunction "RB15*/PWM1L1_P$15") (pintype "bidirectional"))
    )
    (net (code "71") (name "unconnected-(UPIC-RC5*{slash}PMA3-PadP$38)") (class "Default")
      (node (ref "UPIC") (pin "P$38") (pinfunction "RC5*/PMA3_P$38") (pintype "bidirectional"))
    )
    (net (code "72") (name "unconnected-(URF-GDO0{slash}ATEST-Pad6)") (class "Default")
      (node (ref "URF") (pin "6") (pinfunction "GDO0/ATEST_6") (pintype "bidirectional"))
    )
    (net (code "73") (name "unconnected-(URF-GDO2-Pad3)") (class "Default")
      (node (ref "URF") (pin "3") (pinfunction "GDO2_3") (pintype "bidirectional"))
    )
    (net (code "74") (name "unconnected-(UUSB-3V3OUT-Pad17)") (class "Default")
      (node (ref "UUSB") (pin "17") (pinfunction "3V3OUT_17") (pintype "output"))
    )
    (net (code "75") (name "unconnected-(UUSB-CTS-Pad11)") (class "Default")
      (node (ref "UUSB") (pin "11") (pinfunction "CTS_11") (pintype "bidirectional"))
    )
    (net (code "76") (name "unconnected-(UUSB-DTR-Pad2)") (class "Default")
      (node (ref "UUSB") (pin "2") (pinfunction "DTR_2") (pintype "bidirectional"))
    )
    (net (code "77") (name "unconnected-(UUSB-RTS-Pad3)") (class "Default")
      (node (ref "UUSB") (pin "3") (pinfunction "RTS_3") (pintype "bidirectional"))
    )
  )
)
